# LEDs_Sheet.net
KiCad netlist of a schematic drawn in Altium Designer
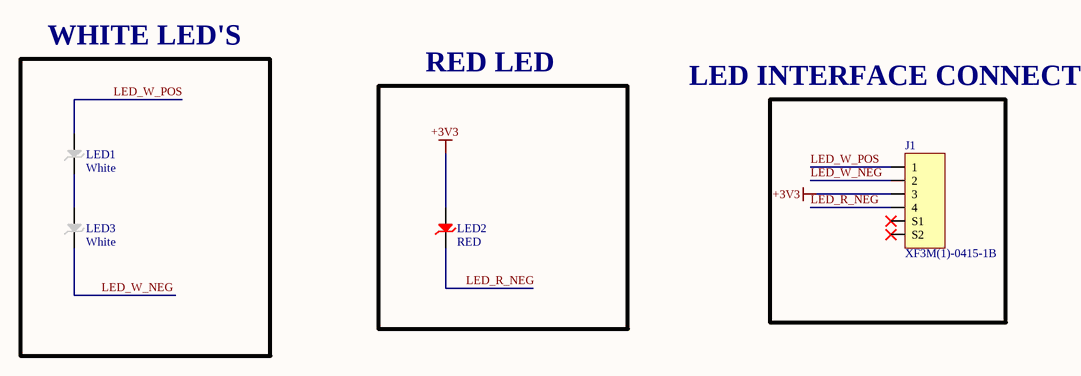
[diagram p0: LEDs_Sheet.SchDoc]

(export (version "E")
  (design (tool "Eeschema 10.0.6"))
  (components
    (comp (ref "J1")
      (value "XF3M(1)-0415-1B")
      (footprint "XF3M(1)-0415-1B")
      (description "4 Position FFC, FPC Connector Contacts, Top and Bottom 0.039\" (1.00mm) Surface Mount, Right Angle")
      (fields
        (field (name "MANUFACTURER") "Omron Electronics Inc-EMC Div")
        (field (name "DIGIKEY PART NUMBER") "OR1210CT-ND")
      )
      (libsource (lib "LED-Driver-Library") (part "XF3M(1)-0415-1B"))
    )
    (comp (ref "LED1")
      (value "White")
      (footprint "LED_SPHRD2L3DH20E7W41J_SAM")
      (description "LED Lighting LH351B White, Cool 5700K 2.8V 350mA 120° 1414 (3535 Metric)")
      (fields
        (field (name "MANUFACTURER") "Samsung Semiconductor, Inc.")
        (field (name "MANUFACTURER PART NUMBER") "SPHWH2L3D30CD4QTP3")
      )
      (libsource (lib "LED-Driver-Library") (part "SPHWH2L3D30CD4QTP3"))
    )
    (comp (ref "LED2")
      (value "RED")
      (footprint "LED_SPHRD2L3DH20E7W41J_SAM")
      (description "LED Lighting Color LH351H Red 660nm (650nm ~ 670nm)")
      (fields
        (field (name "MANUFACTURER") "Samsung Semiconductor, Inc.")
        (field (name "MANUFACTURER PART NUMBER") "SPHRD2L3DH20E7W41J")
      )
      (libsource (lib "LED-Driver-Library") (part "SPHRD2L3DH20E7W41J"))
    )
    (comp (ref "LED3")
      (value "White")
      (footprint "LED_SPHRD2L3DH20E7W41J_SAM")
      (description "LED Lighting LH351B White, Cool 5700K 2.8V 350mA 120° 1414 (3535 Metric)")
      (fields
        (field (name "MANUFACTURER") "Samsung Semiconductor, Inc.")
        (field (name "MANUFACTURER PART NUMBER") "SPHWH2L3D30CD4QTP3")
      )
      (libsource (lib "LED-Driver-Library") (part "SPHWH2L3D30CD4QTP3"))
    )
  )
  (nets
    (net (code "1") (name "+3V3") (class "Default")
      (node (ref "J1") (pin "3") (pinfunction "3_3") (pintype "passive"))
      (node (ref "LED2") (pin "1") (pinfunction "A_1") (pintype "passive"))
    )
    (net (code "2") (name "/LED_R_NEG") (class "Default")
      (node (ref "J1") (pin "4") (pinfunction "4_4") (pintype "passive"))
      (node (ref "LED2") (pin "2") (pinfunction "K_2") (pintype "passive"))
    )
    (net (code "3") (name "/LED_W_NEG") (class "Default")
      (node (ref "J1") (pin "2") (pinfunction "2_2") (pintype "passive"))
      (node (ref "LED3") (pin "2") (pinfunction "K_2") (pintype "passive"))
    )
    (net (code "4") (name "/LED_W_POS") (class "Default")
      (node (ref "J1") (pin "1") (pinfunction "1_1") (pintype "passive"))
      (node (ref "LED1") (pin "1") (pinfunction "A_1") (pintype "passive"))
    )
    (net (code "5") (name "Net-(LED1-K)") (class "Default")
      (node (ref "LED1") (pin "2") (pinfunction "K_2") (pintype "passive"))
      (node (ref "LED3") (pin "1") (pinfunction "A_1") (pintype "passive"))
    )
    (net (code "6") (name "unconnected-(J1-PadS1)") (class "Default")
      (node (ref "J1") (pin "S1") (pinfunction "S1_S1") (pintype "passive+no_connect"))
    )
    (net (code "7") (name "unconnected-(J1-PadS2)") (class "Default")
      (node (ref "J1") (pin "S2") (pinfunction "S2_S2") (pintype "passive"))
    )
  )
)
